# smartTarget.net
KiCad netlist of a schematic drawn in Altium Designer
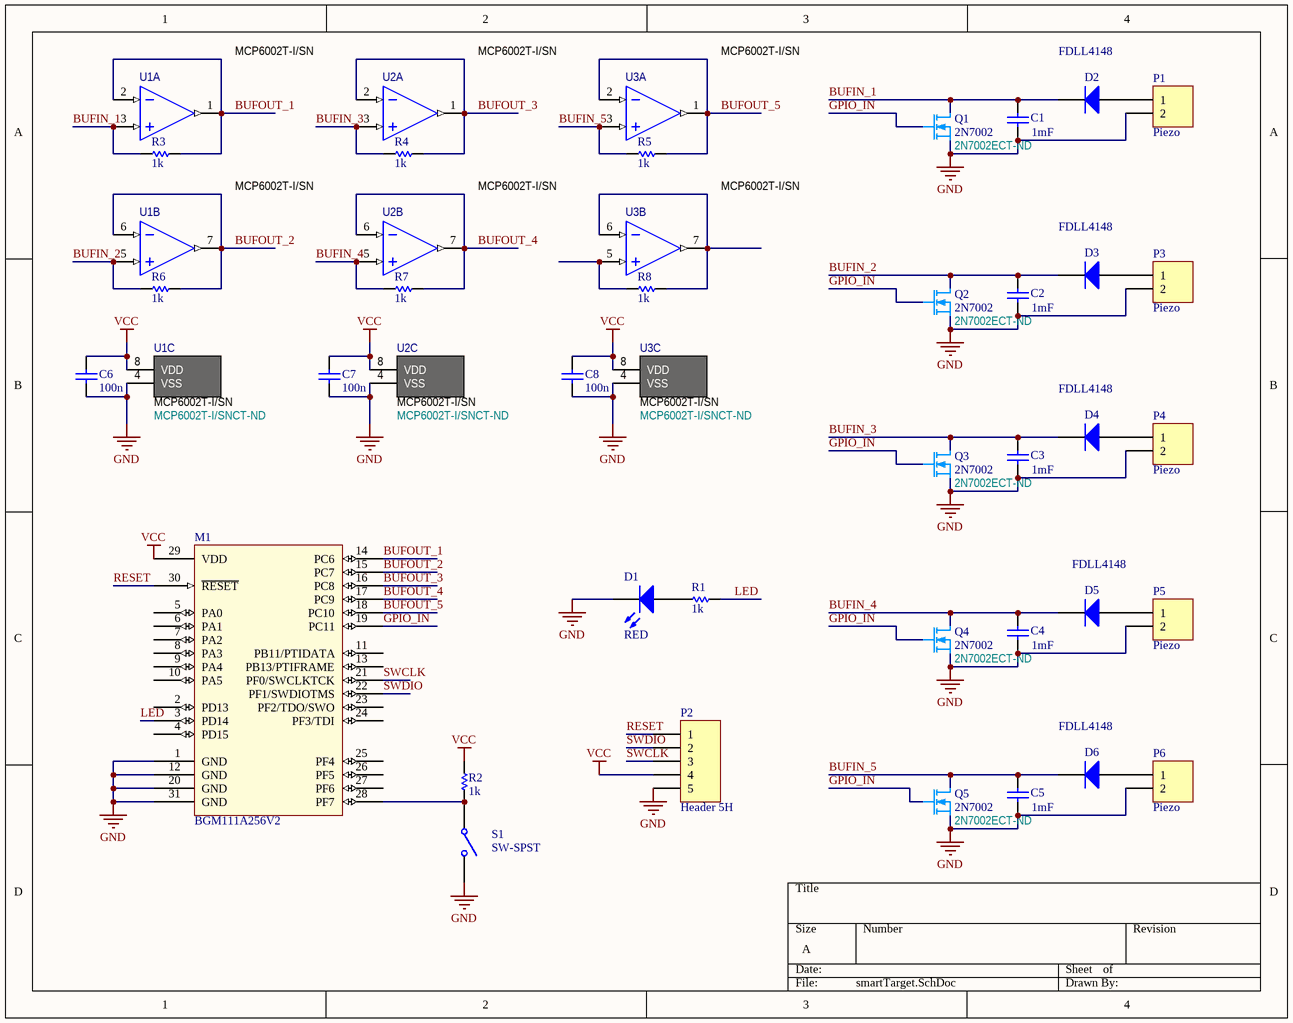
[diagram p0: smartTarget.SchDoc]

(export (version "E")
  (design (tool "Eeschema 10.0.6"))
  (components
    (comp (ref "C1")
      (value "1mF")
      (footprint "CAPC1608N")
      (description "Capacitor (Semiconductor SIM Model)")
      (fields (field (name "PUBLISHER") "Altium Limited"))
      (libsource (lib "Miscellaneous Devices") (part "Cap Semi"))
    )
    (comp (ref "C2")
      (value "1mF")
      (footprint "CAPC1608N")
      (description "Capacitor (Semiconductor SIM Model)")
      (fields (field (name "PUBLISHER") "Altium Limited"))
      (libsource (lib "Miscellaneous Devices") (part "Cap Semi"))
    )
    (comp (ref "C3")
      (value "1mF")
      (footprint "CAPC1608N")
      (description "Capacitor (Semiconductor SIM Model)")
      (fields (field (name "PUBLISHER") "Altium Limited"))
      (libsource (lib "Miscellaneous Devices") (part "Cap Semi"))
    )
    (comp (ref "C4")
      (value "1mF")
      (footprint "CAPC1608N")
      (description "Capacitor (Semiconductor SIM Model)")
      (fields (field (name "PUBLISHER") "Altium Limited"))
      (libsource (lib "Miscellaneous Devices") (part "Cap Semi"))
    )
    (comp (ref "C5")
      (value "1mF")
      (footprint "CAPC1608N")
      (description "Capacitor (Semiconductor SIM Model)")
      (fields (field (name "PUBLISHER") "Altium Limited"))
      (libsource (lib "Miscellaneous Devices") (part "Cap Semi"))
    )
    (comp (ref "C6")
      (value "100n")
      (footprint "CAPC1608N")
      (description "Capacitor (Semiconductor SIM Model)")
      (fields (field (name "PUBLISHER") "Altium Limited"))
      (libsource (lib "Miscellaneous Devices") (part "Cap Semi"))
    )
    (comp (ref "C7")
      (value "100n")
      (footprint "CAPC1608N")
      (description "Capacitor (Semiconductor SIM Model)")
      (fields (field (name "PUBLISHER") "Altium Limited"))
      (libsource (lib "Miscellaneous Devices") (part "Cap Semi"))
    )
    (comp (ref "C8")
      (value "100n")
      (footprint "CAPC1608N")
      (description "Capacitor (Semiconductor SIM Model)")
      (fields (field (name "PUBLISHER") "Altium Limited"))
      (libsource (lib "Miscellaneous Devices") (part "Cap Semi"))
    )
    (comp (ref "D1")
      (value "RED")
      (footprint "LTST-C190EKT")
      (description "Typical RED GaAs LED")
      (fields (field (name "PUBLISHER") "Altium Limited"))
      (libsource (lib "Miscellaneous Devices") (part "LED_RED"))
    )
    (comp (ref "D2")
      (value "FDLL4148")
      (footprint "FAIR-LL-34_V")
      (description "High Conductance Fast Diode, 500 mW, 100 V, -65 to 175 degC, 2-Pin SMD, RoHS, Tape and Reel")
      (fields (field (name "MANUFACTURER") "FairchildSemiconductor"))
      (libsource (lib "Altium Content Vault") (part "D-KA-2"))
    )
    (comp (ref "D3")
      (value "FDLL4148")
      (footprint "FAIR-LL-34_V")
      (description "High Conductance Fast Diode, 500 mW, 100 V, -65 to 175 degC, 2-Pin SMD, RoHS, Tape and Reel")
      (fields (field (name "MANUFACTURER") "FairchildSemiconductor"))
      (libsource (lib "Altium Content Vault") (part "D-KA-2"))
    )
    (comp (ref "D4")
      (value "FDLL4148")
      (footprint "FAIR-LL-34_V")
      (description "High Conductance Fast Diode, 500 mW, 100 V, -65 to 175 degC, 2-Pin SMD, RoHS, Tape and Reel")
      (fields (field (name "MANUFACTURER") "FairchildSemiconductor"))
      (libsource (lib "Altium Content Vault") (part "D-KA-2"))
    )
    (comp (ref "D5")
      (value "FDLL4148")
      (footprint "FAIR-LL-34_V")
      (description "High Conductance Fast Diode, 500 mW, 100 V, -65 to 175 degC, 2-Pin SMD, RoHS, Tape and Reel")
      (fields (field (name "MANUFACTURER") "FairchildSemiconductor"))
      (libsource (lib "Altium Content Vault") (part "D-KA-2"))
    )
    (comp (ref "D6")
      (value "FDLL4148")
      (footprint "FAIR-LL-34_V")
      (description "High Conductance Fast Diode, 500 mW, 100 V, -65 to 175 degC, 2-Pin SMD, RoHS, Tape and Reel")
      (fields (field (name "MANUFACTURER") "FairchildSemiconductor"))
      (libsource (lib "Altium Content Vault") (part "D-KA-2"))
    )
    (comp (ref "M1")
      (value "BGM111A256V2")
      (footprint "BGM111A")
      (description "Blue Gecko Bluetooth 4.1 Module with integrated antenna, 256KB Flash, 32KBRAM")
      (fields (field (name "MANUFACTURER") "Silicon Labs"))
      (libsource (lib "SiLabs Bluetooth Modules") (part "BGM111A256V2"))
    )
    (comp (ref "P1")
      (value "Piezo")
      (footprint "HDR1X2")
      (description "Header, 2-Pin")
      (fields (field (name "PUBLISHER") "Altium Limited"))
      (libsource (lib "Miscellaneous Connectors") (part "Header 2"))
    )
    (comp (ref "P2")
      (value "Header 5H")
      (footprint "HDR1X5H")
      (description "Header, 5-Pin, Right Angle")
      (fields (field (name "PUBLISHER") "Altium Limited"))
      (libsource (lib "Miscellaneous Connectors") (part "Header 5H"))
    )
    (comp (ref "P3")
      (value "Piezo")
      (footprint "HDR1X2")
      (description "Header, 2-Pin")
      (fields (field (name "PUBLISHER") "Altium Limited"))
      (libsource (lib "Miscellaneous Connectors") (part "Header 2"))
    )
    (comp (ref "P4")
      (value "Piezo")
      (footprint "HDR1X2")
      (description "Header, 2-Pin")
      (fields (field (name "PUBLISHER") "Altium Limited"))
      (libsource (lib "Miscellaneous Connectors") (part "Header 2"))
    )
    (comp (ref "P5")
      (value "Piezo")
      (footprint "HDR1X2")
      (description "Header, 2-Pin")
      (fields (field (name "PUBLISHER") "Altium Limited"))
      (libsource (lib "Miscellaneous Connectors") (part "Header 2"))
    )
    (comp (ref "P6")
      (value "Piezo")
      (footprint "HDR1X2")
      (description "Header, 2-Pin")
      (fields (field (name "PUBLISHER") "Altium Limited"))
      (libsource (lib "Miscellaneous Connectors") (part "Header 2"))
    )
    (comp (ref "Q1")
      (value "2N7002")
      (footprint "SOT23-3N")
      (description "2N7002 300mA 60V")
      (fields
        (field (name "SUPPLIER PART NUMBER 1") "2N7002ECT-ND")
        (field (name "PUBLISHER") "Altium Limited")
      )
      (libsource (lib "Miscellaneous Devices") (part "MOSFET-2N7002"))
    )
    (comp (ref "Q2")
      (value "2N7002")
      (footprint "SOT23-3N")
      (description "2N7002 300mA 60V")
      (fields
        (field (name "SUPPLIER PART NUMBER 1") "2N7002ECT-ND")
        (field (name "PUBLISHER") "Altium Limited")
      )
      (libsource (lib "Miscellaneous Devices") (part "MOSFET-2N7002"))
    )
    (comp (ref "Q3")
      (value "2N7002")
      (footprint "SOT23-3N")
      (description "2N7002 300mA 60V")
      (fields
        (field (name "SUPPLIER PART NUMBER 1") "2N7002ECT-ND")
        (field (name "PUBLISHER") "Altium Limited")
      )
      (libsource (lib "Miscellaneous Devices") (part "MOSFET-2N7002"))
    )
    (comp (ref "Q4")
      (value "2N7002")
      (footprint "SOT23-3N")
      (description "2N7002 300mA 60V")
      (fields
        (field (name "SUPPLIER PART NUMBER 1") "2N7002ECT-ND")
        (field (name "PUBLISHER") "Altium Limited")
      )
      (libsource (lib "Miscellaneous Devices") (part "MOSFET-2N7002"))
    )
    (comp (ref "Q5")
      (value "2N7002")
      (footprint "SOT23-3N")
      (description "2N7002 300mA 60V")
      (fields
        (field (name "SUPPLIER PART NUMBER 1") "2N7002ECT-ND")
        (field (name "PUBLISHER") "Altium Limited")
      )
      (libsource (lib "Miscellaneous Devices") (part "MOSFET-2N7002"))
    )
    (comp (ref "R1")
      (value "1k")
      (footprint "RESC1608N")
      (description "Semiconductor Resistor")
      (fields (field (name "PUBLISHER") "Altium Limited"))
      (libsource (lib "Miscellaneous Devices") (part "Res Semi"))
    )
    (comp (ref "R2")
      (value "1k")
      (footprint "RESC1608N")
      (description "Semiconductor Resistor")
      (fields (field (name "PUBLISHER") "Altium Limited"))
      (libsource (lib "Miscellaneous Devices") (part "Res Semi"))
    )
    (comp (ref "R3")
      (value "1k")
      (footprint "RESC1608N")
      (description "Semiconductor Resistor")
      (fields (field (name "PUBLISHER") "Altium Limited"))
      (libsource (lib "Miscellaneous Devices") (part "Res Semi"))
    )
    (comp (ref "R4")
      (value "1k")
      (footprint "RESC1608N")
      (description "Semiconductor Resistor")
      (fields (field (name "PUBLISHER") "Altium Limited"))
      (libsource (lib "Miscellaneous Devices") (part "Res Semi"))
    )
    (comp (ref "R5")
      (value "1k")
      (footprint "RESC1608N")
      (description "Semiconductor Resistor")
      (fields (field (name "PUBLISHER") "Altium Limited"))
      (libsource (lib "Miscellaneous Devices") (part "Res Semi"))
    )
    (comp (ref "R6")
      (value "1k")
      (footprint "RESC1608N")
      (description "Semiconductor Resistor")
      (fields (field (name "PUBLISHER") "Altium Limited"))
      (libsource (lib "Miscellaneous Devices") (part "Res Semi"))
    )
    (comp (ref "R7")
      (value "1k")
      (footprint "RESC1608N")
      (description "Semiconductor Resistor")
      (fields (field (name "PUBLISHER") "Altium Limited"))
      (libsource (lib "Miscellaneous Devices") (part "Res Semi"))
    )
    (comp (ref "R8")
      (value "1k")
      (footprint "RESC1608N")
      (description "Semiconductor Resistor")
      (fields (field (name "PUBLISHER") "Altium Limited"))
      (libsource (lib "Miscellaneous Devices") (part "Res Semi"))
    )
    (comp (ref "S1")
      (value "SW-SPST")
      (footprint "SPST-2")
      (description "Single-Pole, Single-Throw Switch")
      (fields (field (name "PUBLISHER") "Altium Limited"))
      (libsource (lib "Miscellaneous Devices") (part "SW-SPST"))
    )
    (comp (ref "U1")
      (value "MCP6002T-I/SN")
      (footprint "SOIC127P600-8N")
      (description "IC OPAMP GP 1MHZ RRO 8SOIC")
      (fields
        (field (name "MANUFACTURER") "Microchip Technology")
        (field (name "SUPPLIER PART NUMBER 1") "MCP6002T-I/SNCT-ND")
      )
      (libsource (lib "Microchip Op-Amp") (part "MCP6002T-I/SN"))
    )
    (comp (ref "U2")
      (value "MCP6002T-I/SN")
      (footprint "SOIC127P600-8N")
      (description "IC OPAMP GP 1MHZ RRO 8SOIC")
      (fields
        (field (name "MANUFACTURER") "Microchip Technology")
        (field (name "SUPPLIER PART NUMBER 1") "MCP6002T-I/SNCT-ND")
      )
      (libsource (lib "Microchip Op-Amp") (part "MCP6002T-I/SN"))
    )
    (comp (ref "U3")
      (value "MCP6002T-I/SN")
      (footprint "SOIC127P600-8N")
      (description "IC OPAMP GP 1MHZ RRO 8SOIC")
      (fields
        (field (name "MANUFACTURER") "Microchip Technology")
        (field (name "SUPPLIER PART NUMBER 1") "MCP6002T-I/SNCT-ND")
      )
      (libsource (lib "Microchip Op-Amp") (part "MCP6002T-I/SN"))
    )
  )
  (nets
    (net (code "1") (name "/BUFIN_1") (class "Default")
      (node (ref "C1") (pin "2") (pinfunction "2_2") (pintype "passive"))
      (node (ref "D2") (pin "1") (pinfunction "K_1") (pintype "passive"))
      (node (ref "Q1") (pin "3") (pinfunction "D_3") (pintype "passive"))
      (node (ref "R3") (pin "1") (pinfunction "1_1") (pintype "passive"))
      (node (ref "U1") (pin "3") (pinfunction "IN+_3") (pintype "input"))
    )
    (net (code "2") (name "/BUFIN_2") (class "Default")
      (node (ref "C2") (pin "2") (pinfunction "2_2") (pintype "passive"))
      (node (ref "D3") (pin "1") (pinfunction "K_1") (pintype "passive"))
      (node (ref "Q2") (pin "3") (pinfunction "D_3") (pintype "passive"))
      (node (ref "R6") (pin "1") (pinfunction "1_1") (pintype "passive"))
      (node (ref "U1") (pin "5") (pinfunction "IN+_5") (pintype "input"))
    )
    (net (code "3") (name "/BUFIN_3") (class "Default")
      (node (ref "C3") (pin "2") (pinfunction "2_2") (pintype "passive"))
      (node (ref "D4") (pin "1") (pinfunction "K_1") (pintype "passive"))
      (node (ref "Q3") (pin "3") (pinfunction "D_3") (pintype "passive"))
      (node (ref "R4") (pin "1") (pinfunction "1_1") (pintype "passive"))
      (node (ref "U2") (pin "3") (pinfunction "IN+_3") (pintype "input"))
    )
    (net (code "4") (name "/BUFIN_4") (class "Default")
      (node (ref "C4") (pin "2") (pinfunction "2_2") (pintype "passive"))
      (node (ref "D5") (pin "1") (pinfunction "K_1") (pintype "passive"))
      (node (ref "Q4") (pin "3") (pinfunction "D_3") (pintype "passive"))
      (node (ref "R7") (pin "1") (pinfunction "1_1") (pintype "passive"))
      (node (ref "U2") (pin "5") (pinfunction "IN+_5") (pintype "input"))
    )
    (net (code "5") (name "/BUFIN_5") (class "Default")
      (node (ref "C5") (pin "2") (pinfunction "2_2") (pintype "passive"))
      (node (ref "D6") (pin "1") (pinfunction "K_1") (pintype "passive"))
      (node (ref "Q5") (pin "3") (pinfunction "D_3") (pintype "passive"))
      (node (ref "R5") (pin "1") (pinfunction "1_1") (pintype "passive"))
      (node (ref "U3") (pin "3") (pinfunction "IN+_3") (pintype "input"))
    )
    (net (code "6") (name "/BUFOUT_1") (class "Default")
      (node (ref "M1") (pin "14") (pinfunction "PC6_14") (pintype "bidirectional"))
      (node (ref "R3") (pin "2") (pinfunction "2_2") (pintype "passive"))
      (node (ref "U1") (pin "1") (pinfunction "OUT_1") (pintype "output"))
      (node (ref "U1") (pin "2") (pinfunction "IN-_2") (pintype "input"))
    )
    (net (code "7") (name "/BUFOUT_2") (class "Default")
      (node (ref "M1") (pin "15") (pinfunction "PC7_15") (pintype "bidirectional"))
      (node (ref "R6") (pin "2") (pinfunction "2_2") (pintype "passive"))
      (node (ref "U1") (pin "6") (pinfunction "IN-_6") (pintype "input"))
      (node (ref "U1") (pin "7") (pinfunction "OUT_7") (pintype "output"))
    )
    (net (code "8") (name "/BUFOUT_3") (class "Default")
      (node (ref "M1") (pin "16") (pinfunction "PC8_16") (pintype "bidirectional"))
      (node (ref "R4") (pin "2") (pinfunction "2_2") (pintype "passive"))
      (node (ref "U2") (pin "1") (pinfunction "OUT_1") (pintype "output"))
      (node (ref "U2") (pin "2") (pinfunction "IN-_2") (pintype "input"))
    )
    (net (code "9") (name "/BUFOUT_4") (class "Default")
      (node (ref "M1") (pin "17") (pinfunction "PC9_17") (pintype "bidirectional"))
      (node (ref "R7") (pin "2") (pinfunction "2_2") (pintype "passive"))
      (node (ref "U2") (pin "6") (pinfunction "IN-_6") (pintype "input"))
      (node (ref "U2") (pin "7") (pinfunction "OUT_7") (pintype "output"))
    )
    (net (code "10") (name "/BUFOUT_5") (class "Default")
      (node (ref "M1") (pin "18") (pinfunction "PC10_18") (pintype "bidirectional"))
      (node (ref "R5") (pin "2") (pinfunction "2_2") (pintype "passive"))
      (node (ref "U3") (pin "1") (pinfunction "OUT_1") (pintype "output"))
      (node (ref "U3") (pin "2") (pinfunction "IN-_2") (pintype "input"))
    )
    (net (code "11") (name "/GPIO_IN") (class "Default")
      (node (ref "M1") (pin "19") (pinfunction "PC11_19") (pintype "bidirectional"))
      (node (ref "Q1") (pin "1") (pinfunction "G_1") (pintype "passive"))
      (node (ref "Q2") (pin "1") (pinfunction "G_1") (pintype "passive"))
      (node (ref "Q3") (pin "1") (pinfunction "G_1") (pintype "passive"))
      (node (ref "Q4") (pin "1") (pinfunction "G_1") (pintype "passive"))
      (node (ref "Q5") (pin "1") (pinfunction "G_1") (pintype "passive"))
    )
    (net (code "12") (name "/LED") (class "Default")
      (node (ref "M1") (pin "3") (pinfunction "PD14_3") (pintype "bidirectional"))
      (node (ref "R1") (pin "2") (pinfunction "2_2") (pintype "passive"))
    )
    (net (code "13") (name "/RESET") (class "Default")
      (node (ref "M1") (pin "30") (pinfunction "~{RESET}_30") (pintype "input"))
      (node (ref "P2") (pin "1") (pinfunction "1_1") (pintype "passive"))
    )
    (net (code "14") (name "/SWCLK") (class "Default")
      (node (ref "M1") (pin "21") (pinfunction "PF0/SWCLKTCK_21") (pintype "bidirectional"))
      (node (ref "P2") (pin "3") (pinfunction "3_3") (pintype "passive"))
    )
    (net (code "15") (name "/SWDIO") (class "Default")
      (node (ref "M1") (pin "22") (pinfunction "PF1/SWDIOTMS_22") (pintype "bidirectional"))
      (node (ref "P2") (pin "2") (pinfunction "2_2") (pintype "passive"))
    )
    (net (code "16") (name "GND") (class "Default")
      (node (ref "C1") (pin "1") (pinfunction "1_1") (pintype "passive"))
      (node (ref "C2") (pin "1") (pinfunction "1_1") (pintype "passive"))
      (node (ref "C3") (pin "1") (pinfunction "1_1") (pintype "passive"))
      (node (ref "C4") (pin "1") (pinfunction "1_1") (pintype "passive"))
      (node (ref "C5") (pin "1") (pinfunction "1_1") (pintype "passive"))
      (node (ref "C6") (pin "2") (pinfunction "2_2") (pintype "passive"))
      (node (ref "C7") (pin "2") (pinfunction "2_2") (pintype "passive"))
      (node (ref "C8") (pin "2") (pinfunction "2_2") (pintype "passive"))
      (node (ref "D1") (pin "2") (pinfunction "K_2") (pintype "passive"))
      (node (ref "M1") (pin "1") (pinfunction "GND_1") (pintype "power_in"))
      (node (ref "M1") (pin "12") (pinfunction "GND_12") (pintype "power_in"))
      (node (ref "M1") (pin "20") (pinfunction "GND_20") (pintype "power_in"))
      (node (ref "M1") (pin "31") (pinfunction "GND_31") (pintype "power_in"))
      (node (ref "P1") (pin "2") (pinfunction "2_2") (pintype "passive"))
      (node (ref "P2") (pin "5") (pinfunction "5_5") (pintype "passive"))
      (node (ref "P3") (pin "2") (pinfunction "2_2") (pintype "passive"))
      (node (ref "P4") (pin "2") (pinfunction "2_2") (pintype "passive"))
      (node (ref "P5") (pin "2") (pinfunction "2_2") (pintype "passive"))
      (node (ref "P6") (pin "2") (pinfunction "2_2") (pintype "passive"))
      (node (ref "Q1") (pin "2") (pinfunction "S_2") (pintype "passive"))
      (node (ref "Q2") (pin "2") (pinfunction "S_2") (pintype "passive"))
      (node (ref "Q3") (pin "2") (pinfunction "S_2") (pintype "passive"))
      (node (ref "Q4") (pin "2") (pinfunction "S_2") (pintype "passive"))
      (node (ref "Q5") (pin "2") (pinfunction "S_2") (pintype "passive"))
      (node (ref "S1") (pin "2") (pinfunction "NO_2") (pintype "passive"))
      (node (ref "U1") (pin "4") (pinfunction "VSS_4") (pintype "power_in"))
      (node (ref "U2") (pin "4") (pinfunction "VSS_4") (pintype "power_in"))
      (node (ref "U3") (pin "4") (pinfunction "VSS_4") (pintype "power_in"))
    )
    (net (code "17") (name "Net-(D1-A)") (class "Default")
      (node (ref "D1") (pin "1") (pinfunction "A_1") (pintype "passive"))
      (node (ref "R1") (pin "1") (pinfunction "1_1") (pintype "passive"))
    )
    (net (code "18") (name "Net-(D2-A)") (class "Default")
      (node (ref "D2") (pin "2") (pinfunction "A_2") (pintype "passive"))
      (node (ref "P1") (pin "1") (pinfunction "1_1") (pintype "passive"))
    )
    (net (code "19") (name "Net-(D3-A)") (class "Default")
      (node (ref "D3") (pin "2") (pinfunction "A_2") (pintype "passive"))
      (node (ref "P3") (pin "1") (pinfunction "1_1") (pintype "passive"))
    )
    (net (code "20") (name "Net-(D4-A)") (class "Default")
      (node (ref "D4") (pin "2") (pinfunction "A_2") (pintype "passive"))
      (node (ref "P4") (pin "1") (pinfunction "1_1") (pintype "passive"))
    )
    (net (code "21") (name "Net-(D5-A)") (class "Default")
      (node (ref "D5") (pin "2") (pinfunction "A_2") (pintype "passive"))
      (node (ref "P5") (pin "1") (pinfunction "1_1") (pintype "passive"))
    )
    (net (code "22") (name "Net-(D6-A)") (class "Default")
      (node (ref "D6") (pin "2") (pinfunction "A_2") (pintype "passive"))
      (node (ref "P6") (pin "1") (pinfunction "1_1") (pintype "passive"))
    )
    (net (code "23") (name "Net-(M1-PF7)") (class "Default")
      (node (ref "M1") (pin "28") (pinfunction "PF7_28") (pintype "bidirectional"))
      (node (ref "R2") (pin "1") (pinfunction "1_1") (pintype "passive"))
      (node (ref "S1") (pin "1") (pinfunction "COMMON_1") (pintype "passive"))
    )
    (net (code "24") (name "Net-(U3B-IN+)") (class "Default")
      (node (ref "R8") (pin "1") (pinfunction "1_1") (pintype "passive"))
      (node (ref "U3") (pin "5") (pinfunction "IN+_5") (pintype "input"))
    )
    (net (code "25") (name "Net-(U3B-IN-)") (class "Default")
      (node (ref "R8") (pin "2") (pinfunction "2_2") (pintype "passive"))
      (node (ref "U3") (pin "6") (pinfunction "IN-_6") (pintype "input"))
      (node (ref "U3") (pin "7") (pinfunction "OUT_7") (pintype "output"))
    )
    (net (code "26") (name "VCC") (class "Default")
      (node (ref "C6") (pin "1") (pinfunction "1_1") (pintype "passive"))
      (node (ref "C7") (pin "1") (pinfunction "1_1") (pintype "passive"))
      (node (ref "C8") (pin "1") (pinfunction "1_1") (pintype "passive"))
      (node (ref "M1") (pin "29") (pinfunction "VDD_29") (pintype "power_in"))
      (node (ref "P2") (pin "4") (pinfunction "4_4") (pintype "passive"))
      (node (ref "R2") (pin "2") (pinfunction "2_2") (pintype "passive"))
      (node (ref "U1") (pin "8") (pinfunction "VDD_8") (pintype "power_in"))
      (node (ref "U2") (pin "8") (pinfunction "VDD_8") (pintype "power_in"))
      (node (ref "U3") (pin "8") (pinfunction "VDD_8") (pintype "power_in"))
    )
    (net (code "27") (name "unconnected-(M1-PA0-Pad5)") (class "Default")
      (node (ref "M1") (pin "5") (pinfunction "PA0_5") (pintype "bidirectional"))
    )
    (net (code "28") (name "unconnected-(M1-PA1-Pad6)") (class "Default")
      (node (ref "M1") (pin "6") (pinfunction "PA1_6") (pintype "bidirectional"))
    )
    (net (code "29") (name "unconnected-(M1-PA2-Pad7)") (class "Default")
      (node (ref "M1") (pin "7") (pinfunction "PA2_7") (pintype "bidirectional"))
    )
    (net (code "30") (name "unconnected-(M1-PA3-Pad8)") (class "Default")
      (node (ref "M1") (pin "8") (pinfunction "PA3_8") (pintype "bidirectional"))
    )
    (net (code "31") (name "unconnected-(M1-PA4-Pad9)") (class "Default")
      (node (ref "M1") (pin "9") (pinfunction "PA4_9") (pintype "bidirectional"))
    )
    (net (code "32") (name "unconnected-(M1-PA5-Pad10)") (class "Default")
      (node (ref "M1") (pin "10") (pinfunction "PA5_10") (pintype "bidirectional"))
    )
    (net (code "33") (name "unconnected-(M1-PB11{slash}PTIDATA-Pad11)") (class "Default")
      (node (ref "M1") (pin "11") (pinfunction "PB11/PTIDATA_11") (pintype "bidirectional"))
    )
    (net (code "34") (name "unconnected-(M1-PB13{slash}PTIFRAME-Pad13)") (class "Default")
      (node (ref "M1") (pin "13") (pinfunction "PB13/PTIFRAME_13") (pintype "bidirectional"))
    )
    (net (code "35") (name "unconnected-(M1-PD13-Pad2)") (class "Default")
      (node (ref "M1") (pin "2") (pinfunction "PD13_2") (pintype "bidirectional"))
    )
    (net (code "36") (name "unconnected-(M1-PD15-Pad4)") (class "Default")
      (node (ref "M1") (pin "4") (pinfunction "PD15_4") (pintype "bidirectional"))
    )
    (net (code "37") (name "unconnected-(M1-PF2{slash}TDO{slash}SWO-Pad23)") (class "Default")
      (node (ref "M1") (pin "23") (pinfunction "PF2/TDO/SWO_23") (pintype "bidirectional"))
    )
    (net (code "38") (name "unconnected-(M1-PF3{slash}TDI-Pad24)") (class "Default")
      (node (ref "M1") (pin "24") (pinfunction "PF3/TDI_24") (pintype "bidirectional"))
    )
    (net (code "39") (name "unconnected-(M1-PF4-Pad25)") (class "Default")
      (node (ref "M1") (pin "25") (pinfunction "PF4_25") (pintype "bidirectional"))
    )
    (net (code "40") (name "unconnected-(M1-PF5-Pad26)") (class "Default")
      (node (ref "M1") (pin "26") (pinfunction "PF5_26") (pintype "bidirectional"))
    )
    (net (code "41") (name "unconnected-(M1-PF6-Pad27)") (class "Default")
      (node (ref "M1") (pin "27") (pinfunction "PF6_27") (pintype "bidirectional"))
    )
  )
)
